# OpticalSpeedometerV1.net
KiCad netlist of a schematic drawn in EAGLE
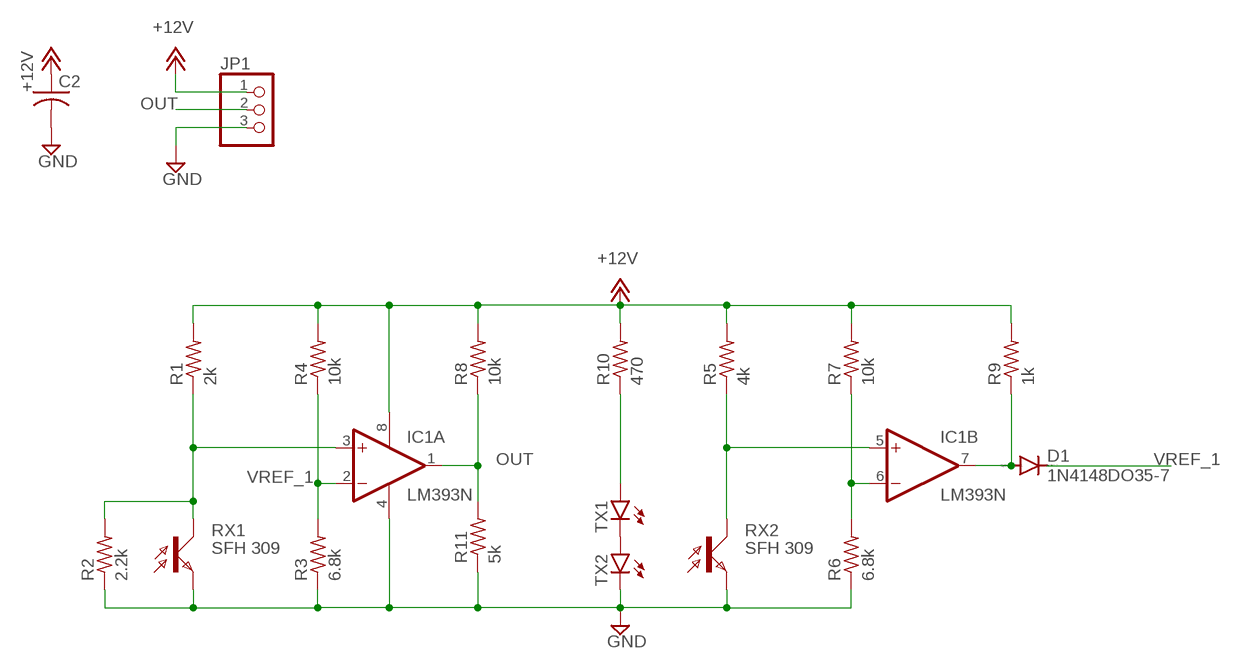
[diagram p0: schematic, sheet 1]

(export (version "E")
  (design (tool "Eeschema 10.0.6"))
  (components
    (comp (ref "C2")
      (value "C-US050-050X075")
      (footprint "eagle-import:C050-050X075")
      (libsource (lib "eagle-import") (part "C-US050-050X075"))
    )
    (comp (ref "D1")
      (value "1N4148DO35-7")
      (footprint "eagle-import:DO35-7")
      (libsource (lib "eagle-import") (part "1N4148DO35-7"))
    )
    (comp (ref "IC1")
      (value "LM393N")
      (footprint "eagle-import:DIL08")
      (libsource (lib "eagle-import") (part "LM393N"))
    )
    (comp (ref "JP1")
      (value "PINHD-1X3")
      (footprint "eagle-import:1X03")
      (libsource (lib "eagle-import") (part "PINHD-1X3"))
    )
    (comp (ref "R1")
      (value "2k")
      (footprint "eagle-import:0204_5")
      (libsource (lib "eagle-import") (part "R-US_0204/5"))
    )
    (comp (ref "R2")
      (value "2.2k")
      (footprint "eagle-import:0204_5")
      (libsource (lib "eagle-import") (part "R-US_0204/5"))
    )
    (comp (ref "R3")
      (value "6.8k")
      (footprint "eagle-import:0204_5")
      (libsource (lib "eagle-import") (part "R-US_0204/5"))
    )
    (comp (ref "R4")
      (value "10k")
      (footprint "eagle-import:0204_5")
      (libsource (lib "eagle-import") (part "R-US_0204/5"))
    )
    (comp (ref "R5")
      (value "4k")
      (footprint "eagle-import:0204_5")
      (libsource (lib "eagle-import") (part "R-US_0204/5"))
    )
    (comp (ref "R6")
      (value "6.8k")
      (footprint "eagle-import:0204_5")
      (libsource (lib "eagle-import") (part "R-US_0204/5"))
    )
    (comp (ref "R7")
      (value "10k")
      (footprint "eagle-import:0204_5")
      (libsource (lib "eagle-import") (part "R-US_0204/5"))
    )
    (comp (ref "R8")
      (value "10k")
      (footprint "eagle-import:0204_5")
      (libsource (lib "eagle-import") (part "R-US_0204/5"))
    )
    (comp (ref "R9")
      (value "1k")
      (footprint "eagle-import:0204_5")
      (libsource (lib "eagle-import") (part "R-US_0204/5"))
    )
    (comp (ref "R10")
      (value "470")
      (footprint "eagle-import:0204_5")
      (libsource (lib "eagle-import") (part "R-US_0204/5"))
    )
    (comp (ref "R11")
      (value "5k")
      (footprint "eagle-import:0204_5")
      (libsource (lib "eagle-import") (part "R-US_0204/5"))
    )
    (comp (ref "RX1")
      (value "SFH 309")
      (footprint "eagle-import:BPX81")
      (libsource (lib "eagle-import") (part "BPX81"))
    )
    (comp (ref "RX2")
      (value "SFH 309")
      (footprint "eagle-import:BPX81")
      (libsource (lib "eagle-import") (part "BPX81"))
    )
    (comp (ref "TX1")
      (value "LED3MM")
      (footprint "eagle-import:LED3MM")
      (libsource (lib "eagle-import") (part "LED3MM"))
    )
    (comp (ref "TX2")
      (value "LED3MM")
      (footprint "eagle-import:LED3MM")
      (libsource (lib "eagle-import") (part "LED3MM"))
    )
  )
  (nets
    (net (code "1") (name "+12V") (class "Default")
      (node (ref "C2") (pin "1") (pinfunction "1_1") (pintype "passive"))
      (node (ref "IC1") (pin "8") (pinfunction "V+_8") (pintype "power_in"))
      (node (ref "JP1") (pin "1") (pinfunction "1_1") (pintype "passive"))
      (node (ref "R1") (pin "2") (pinfunction "2_2") (pintype "passive"))
      (node (ref "R10") (pin "2") (pinfunction "2_2") (pintype "passive"))
      (node (ref "R4") (pin "2") (pinfunction "2_2") (pintype "passive"))
      (node (ref "R5") (pin "2") (pinfunction "2_2") (pintype "passive"))
      (node (ref "R7") (pin "2") (pinfunction "2_2") (pintype "passive"))
      (node (ref "R8") (pin "2") (pinfunction "2_2") (pintype "passive"))
      (node (ref "R9") (pin "2") (pinfunction "2_2") (pintype "passive"))
    )
    (net (code "2") (name "/OUT") (class "Default")
      (node (ref "IC1") (pin "1") (pinfunction "OUT_1") (pintype "output"))
      (node (ref "JP1") (pin "2") (pinfunction "2_2") (pintype "passive"))
      (node (ref "R11") (pin "2") (pinfunction "2_2") (pintype "passive"))
      (node (ref "R8") (pin "1") (pinfunction "1_1") (pintype "passive"))
    )
    (net (code "3") (name "/VREF_1") (class "Default")
      (node (ref "D1") (pin "C") (pinfunction "C_C") (pintype "passive"))
      (node (ref "IC1") (pin "2") (pinfunction "-IN_2") (pintype "input"))
      (node (ref "R3") (pin "2") (pinfunction "2_2") (pintype "passive"))
      (node (ref "R4") (pin "1") (pinfunction "1_1") (pintype "passive"))
    )
    (net (code "4") (name "GND") (class "Default")
      (node (ref "C2") (pin "2") (pinfunction "2_2") (pintype "passive"))
      (node (ref "IC1") (pin "4") (pinfunction "V-_4") (pintype "power_in"))
      (node (ref "JP1") (pin "3") (pinfunction "3_3") (pintype "passive"))
      (node (ref "R11") (pin "1") (pinfunction "1_1") (pintype "passive"))
      (node (ref "R2") (pin "1") (pinfunction "1_1") (pintype "passive"))
      (node (ref "R3") (pin "1") (pinfunction "1_1") (pintype "passive"))
      (node (ref "R6") (pin "1") (pinfunction "1_1") (pintype "passive"))
      (node (ref "RX1") (pin "E") (pinfunction "E_E") (pintype "passive"))
      (node (ref "RX2") (pin "E") (pinfunction "E_E") (pintype "passive"))
      (node (ref "TX2") (pin "K") (pinfunction "C_K") (pintype "passive"))
    )
    (net (code "5") (name "Net-(IC1A-+IN)") (class "Default")
      (node (ref "IC1") (pin "3") (pinfunction "+IN_3") (pintype "input"))
      (node (ref "R1") (pin "1") (pinfunction "1_1") (pintype "passive"))
      (node (ref "R2") (pin "2") (pinfunction "2_2") (pintype "passive"))
      (node (ref "RX1") (pin "C") (pinfunction "C_C") (pintype "passive"))
    )
    (net (code "6") (name "Net-(IC1B-+IN)") (class "Default")
      (node (ref "IC1") (pin "5") (pinfunction "+IN_5") (pintype "input"))
      (node (ref "R5") (pin "1") (pinfunction "1_1") (pintype "passive"))
      (node (ref "RX2") (pin "C") (pinfunction "C_C") (pintype "passive"))
    )
    (net (code "7") (name "Net-(IC1B--IN)") (class "Default")
      (node (ref "IC1") (pin "6") (pinfunction "-IN_6") (pintype "input"))
      (node (ref "R6") (pin "2") (pinfunction "2_2") (pintype "passive"))
      (node (ref "R7") (pin "1") (pinfunction "1_1") (pintype "passive"))
    )
    (net (code "8") (name "Net-(IC1B-OUT)") (class "Default")
      (node (ref "D1") (pin "A") (pinfunction "A_A") (pintype "passive"))
      (node (ref "IC1") (pin "7") (pinfunction "OUT_7") (pintype "output"))
      (node (ref "R9") (pin "1") (pinfunction "1_1") (pintype "passive"))
    )
    (net (code "9") (name "Net-(R10-Pad1)") (class "Default")
      (node (ref "R10") (pin "1") (pinfunction "1_1") (pintype "passive"))
      (node (ref "TX1") (pin "A") (pinfunction "A_A") (pintype "passive"))
    )
    (net (code "10") (name "Net-(TX1-C)") (class "Default")
      (node (ref "TX1") (pin "K") (pinfunction "C_K") (pintype "passive"))
      (node (ref "TX2") (pin "A") (pinfunction "A_A") (pintype "passive"))
    )
  )
)
